# Sheet1.net
KiCad netlist of a schematic drawn in Altium Designer
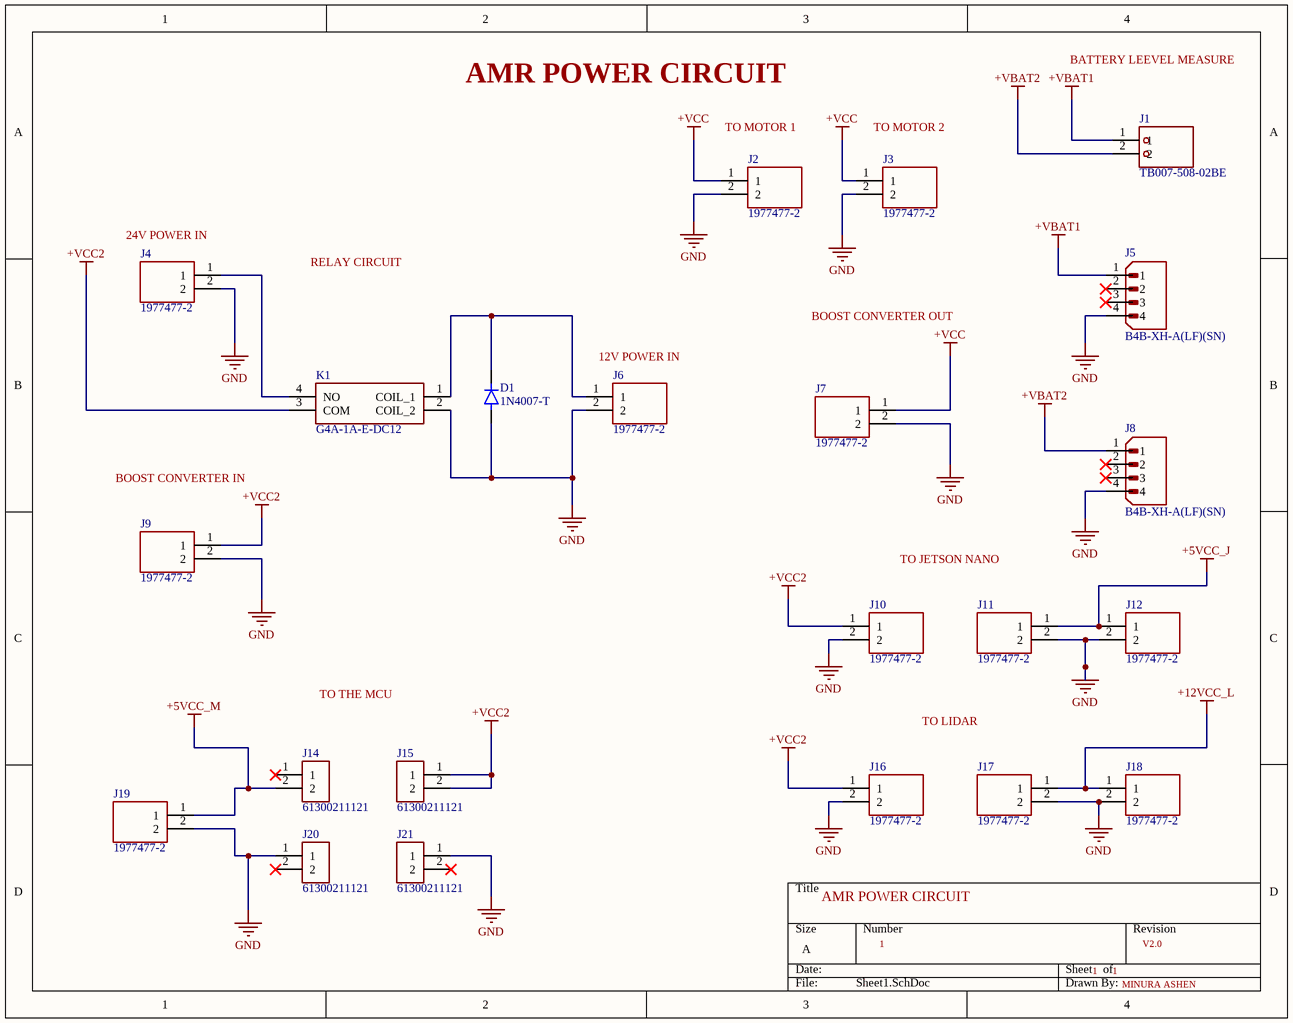
[diagram p0: Sheet1.SchDoc]

(export (version "E")
  (design (tool "Eeschema 10.0.6"))
  (components
    (comp (ref "D1")
      (value "1N4007-T")
      (footprint "DIOAD780W78L463D236")
      (description "Diode Standard 1000 V 1A Through Hole DO-41")
      (fields (field (name "MF") "Yangjie Technology") (field (name "MP") "1N4007"))
      (libsource (lib "Schlib2") (part "1N4007-T"))
    )
    (comp (ref "J1")
      (value "TB007-508-02BE")
      (footprint "CUI_TB007-508-02BE")
      (description "2~24 Poles, Screw Type, Horizontal, 5.08 Pitch, 24~12 (AWG), Terminal Block Connector")
      (fields (field (name "MF") "Same Sky"))
      (libsource (lib "Schlib2") (part "TB007-508-02BE"))
    )
    (comp (ref "J2")
      (value "1977477-2")
      (footprint "TE_1977477-2")
      (description "Buchanan, Module Dual Barrier, .325 CL, 2 Pos. ¦ TE Connectivity 1977477-2")
      (fields (field (name "MF") "TE Connectivity"))
      (libsource (lib "Schlib2") (part "1977477-2"))
    )
    (comp (ref "J3")
      (value "1977477-2")
      (footprint "TE_1977477-2")
      (description "Buchanan, Module Dual Barrier, .325 CL, 2 Pos. ¦ TE Connectivity 1977477-2")
      (fields (field (name "MF") "TE Connectivity"))
      (libsource (lib "Schlib2") (part "1977477-2"))
    )
    (comp (ref "J4")
      (value "1977477-2")
      (footprint "TE_1977477-2")
      (description "Buchanan, Module Dual Barrier, .325 CL, 2 Pos. ¦ TE Connectivity 1977477-2")
      (fields (field (name "MF") "TE Connectivity"))
      (libsource (lib "") (part "1977477-2_1"))
    )
    (comp (ref "J5")
      (value "B4B-XH-A(LF)(SN)")
      (footprint "JST_B4B-XH-A(LF)(SN)")
      (description "Connector Header Through Hole 4 position 0.098 (2.50mm)")
      (fields (field (name "MF") "JST Sales"))
      (libsource (lib "Schlib2") (part "B4B-XH-A(LF)(SN)"))
    )
    (comp (ref "J6")
      (value "1977477-2")
      (footprint "TE_1977477-2")
      (description "Buchanan, Module Dual Barrier, .325 CL, 2 Pos. ¦ TE Connectivity 1977477-2")
      (fields (field (name "MF") "TE Connectivity"))
      (libsource (lib "Schlib2") (part "1977477-2"))
    )
    (comp (ref "J7")
      (value "1977477-2")
      (footprint "TE_1977477-2")
      (description "Buchanan, Module Dual Barrier, .325 CL, 2 Pos. ¦ TE Connectivity 1977477-2")
      (fields (field (name "MF") "TE Connectivity"))
      (libsource (lib "") (part "1977477-2_1"))
    )
    (comp (ref "J8")
      (value "B4B-XH-A(LF)(SN)")
      (footprint "JST_B4B-XH-A(LF)(SN)")
      (description "Connector Header Through Hole 4 position 0.098 (2.50mm)")
      (fields (field (name "MF") "JST Sales"))
      (libsource (lib "Schlib2") (part "B4B-XH-A(LF)(SN)"))
    )
    (comp (ref "J9")
      (value "1977477-2")
      (footprint "TE_1977477-2")
      (description "Buchanan, Module Dual Barrier, .325 CL, 2 Pos. ¦ TE Connectivity 1977477-2")
      (fields (field (name "MF") "TE Connectivity"))
      (libsource (lib "") (part "1977477-2_1"))
    )
    (comp (ref "J10")
      (value "1977477-2")
      (footprint "TE_1977477-2")
      (description "Buchanan, Module Dual Barrier, .325 CL, 2 Pos. ¦ TE Connectivity 1977477-2")
      (fields (field (name "MF") "TE Connectivity"))
      (libsource (lib "Schlib2") (part "1977477-2"))
    )
    (comp (ref "J11")
      (value "1977477-2")
      (footprint "TE_1977477-2")
      (description "Buchanan, Module Dual Barrier, .325 CL, 2 Pos. ¦ TE Connectivity 1977477-2")
      (fields (field (name "MF") "TE Connectivity"))
      (libsource (lib "") (part "1977477-2_1"))
    )
    (comp (ref "J12")
      (value "1977477-2")
      (footprint "TE_1977477-2")
      (description "Buchanan, Module Dual Barrier, .325 CL, 2 Pos. ¦ TE Connectivity 1977477-2")
      (fields (field (name "MF") "TE Connectivity"))
      (libsource (lib "Schlib2") (part "1977477-2"))
    )
    (comp (ref "J14")
      (value "61300211121")
      (footprint "HDRV2W110P0X254_1X2_508X254X854P")
      (description "WURTH ELEKTRONIK - 61300211121 - HEADER, 2.54MM, PIN, THT, VERTICAL, 2WAY")
      (fields (field (name "MOUSER PART NUMBER") "710-61300211121"))
      (libsource (lib "Schlib2") (part "61300211121"))
    )
    (comp (ref "J15")
      (value "61300211121")
      (footprint "HDRV2W110P0X254_1X2_508X254X854P")
      (description "WURTH ELEKTRONIK - 61300211121 - HEADER, 2.54MM, PIN, THT, VERTICAL, 2WAY")
      (fields (field (name "MOUSER PART NUMBER") "710-61300211121"))
      (libsource (lib "") (part "61300211121_1"))
    )
    (comp (ref "J16")
      (value "1977477-2")
      (footprint "TE_1977477-2")
      (description "Buchanan, Module Dual Barrier, .325 CL, 2 Pos. ¦ TE Connectivity 1977477-2")
      (fields (field (name "MF") "TE Connectivity"))
      (libsource (lib "Schlib2") (part "1977477-2"))
    )
    (comp (ref "J17")
      (value "1977477-2")
      (footprint "TE_1977477-2")
      (description "Buchanan, Module Dual Barrier, .325 CL, 2 Pos. ¦ TE Connectivity 1977477-2")
      (fields (field (name "MF") "TE Connectivity"))
      (libsource (lib "") (part "1977477-2_1"))
    )
    (comp (ref "J18")
      (value "1977477-2")
      (footprint "TE_1977477-2")
      (description "Buchanan, Module Dual Barrier, .325 CL, 2 Pos. ¦ TE Connectivity 1977477-2")
      (fields (field (name "MF") "TE Connectivity"))
      (libsource (lib "Schlib2") (part "1977477-2"))
    )
    (comp (ref "J19")
      (value "1977477-2")
      (footprint "TE_1977477-2")
      (description "Buchanan, Module Dual Barrier, .325 CL, 2 Pos. ¦ TE Connectivity 1977477-2")
      (fields (field (name "MF") "TE Connectivity"))
      (libsource (lib "") (part "1977477-2_1"))
    )
    (comp (ref "J20")
      (value "61300211121")
      (footprint "HDRV2W110P0X254_1X2_508X254X854P")
      (description "WURTH ELEKTRONIK - 61300211121 - HEADER, 2.54MM, PIN, THT, VERTICAL, 2WAY")
      (fields (field (name "MOUSER PART NUMBER") "710-61300211121"))
      (libsource (lib "Schlib2") (part "61300211121"))
    )
    (comp (ref "J21")
      (value "61300211121")
      (footprint "HDRV2W110P0X254_1X2_508X254X854P")
      (description "WURTH ELEKTRONIK - 61300211121 - HEADER, 2.54MM, PIN, THT, VERTICAL, 2WAY")
      (fields (field (name "MOUSER PART NUMBER") "710-61300211121"))
      (libsource (lib "") (part "61300211121_1"))
    )
    (comp (ref "K1")
      (value "G4A-1A-E-DC12")
      (footprint "G4A1AEDC12")
      (description "General Purpose Relays SPST-NO 12VDC PCB & QC")
      (fields (field (name "MOUSER PART NUMBER") "653-G4A-1AE-DC12"))
      (libsource (lib "Schlib2") (part "G4A-1A-E-DC12"))
    )
  )
  (nets
    (net (code "1") (name "+5VCC_J") (class "Default")
      (node (ref "J11") (pin "1") (pinfunction "1_1") (pintype "passive"))
      (node (ref "J12") (pin "1") (pinfunction "1_1") (pintype "passive"))
    )
    (net (code "2") (name "+5VCC_M") (class "Default")
      (node (ref "J14") (pin "2") (pinfunction "2_2") (pintype "passive"))
      (node (ref "J19") (pin "1") (pinfunction "1_1") (pintype "passive"))
    )
    (net (code "3") (name "+12VCC_L") (class "Default")
      (node (ref "J17") (pin "1") (pinfunction "1_1") (pintype "passive"))
      (node (ref "J18") (pin "1") (pinfunction "1_1") (pintype "passive"))
    )
    (net (code "4") (name "+VBAT1") (class "Default")
      (node (ref "J1") (pin "1") (pinfunction "1_1") (pintype "passive"))
      (node (ref "J5") (pin "1") (pinfunction "1_1") (pintype "passive"))
    )
    (net (code "5") (name "+VBAT2") (class "Default")
      (node (ref "J1") (pin "2") (pinfunction "2_2") (pintype "passive"))
      (node (ref "J8") (pin "1") (pinfunction "1_1") (pintype "passive"))
    )
    (net (code "6") (name "+VCC") (class "Default")
      (node (ref "J2") (pin "1") (pinfunction "1_1") (pintype "passive"))
      (node (ref "J3") (pin "1") (pinfunction "1_1") (pintype "passive"))
      (node (ref "J7") (pin "1") (pinfunction "1_1") (pintype "passive"))
    )
    (net (code "7") (name "+VCC2") (class "Default")
      (node (ref "J10") (pin "1") (pinfunction "1_1") (pintype "passive"))
      (node (ref "J15") (pin "1") (pinfunction "1_1") (pintype "passive"))
      (node (ref "J15") (pin "2") (pinfunction "2_2") (pintype "passive"))
      (node (ref "J16") (pin "1") (pinfunction "1_1") (pintype "passive"))
      (node (ref "J9") (pin "1") (pinfunction "1_1") (pintype "passive"))
      (node (ref "K1") (pin "3") (pinfunction "COM_3") (pintype "passive"))
    )
    (net (code "8") (name "GND") (class "Default")
      (node (ref "D1") (pin "A") (pinfunction "A_A") (pintype "passive"))
      (node (ref "J10") (pin "2") (pinfunction "2_2") (pintype "passive"))
      (node (ref "J11") (pin "2") (pinfunction "2_2") (pintype "passive"))
      (node (ref "J12") (pin "2") (pinfunction "2_2") (pintype "passive"))
      (node (ref "J16") (pin "2") (pinfunction "2_2") (pintype "passive"))
      (node (ref "J17") (pin "2") (pinfunction "2_2") (pintype "passive"))
      (node (ref "J18") (pin "2") (pinfunction "2_2") (pintype "passive"))
      (node (ref "J19") (pin "2") (pinfunction "2_2") (pintype "passive"))
      (node (ref "J2") (pin "2") (pinfunction "2_2") (pintype "passive"))
      (node (ref "J20") (pin "1") (pinfunction "1_1") (pintype "passive"))
      (node (ref "J21") (pin "1") (pinfunction "1_1") (pintype "passive"))
      (node (ref "J3") (pin "2") (pinfunction "2_2") (pintype "passive"))
      (node (ref "J4") (pin "2") (pinfunction "2_2") (pintype "passive"))
      (node (ref "J5") (pin "4") (pinfunction "4_4") (pintype "passive"))
      (node (ref "J6") (pin "2") (pinfunction "2_2") (pintype "passive"))
      (node (ref "J7") (pin "2") (pinfunction "2_2") (pintype "passive"))
      (node (ref "J8") (pin "4") (pinfunction "4_4") (pintype "passive"))
      (node (ref "J9") (pin "2") (pinfunction "2_2") (pintype "passive"))
      (node (ref "K1") (pin "2") (pinfunction "COIL_2_2") (pintype "passive"))
    )
    (net (code "9") (name "Net-(K1-COIL_1)") (class "Default")
      (node (ref "D1") (pin "K") (pinfunction "K_K") (pintype "passive"))
      (node (ref "J6") (pin "1") (pinfunction "1_1") (pintype "passive"))
      (node (ref "K1") (pin "1") (pinfunction "COIL_1_1") (pintype "passive"))
    )
    (net (code "10") (name "Net-(K1-NO)") (class "Default")
      (node (ref "J4") (pin "1") (pinfunction "1_1") (pintype "passive"))
      (node (ref "K1") (pin "4") (pinfunction "NO_4") (pintype "passive"))
    )
    (net (code "11") (name "unconnected-(J5-Pad2)") (class "Default")
      (node (ref "J5") (pin "2") (pinfunction "2_2") (pintype "passive+no_connect"))
    )
    (net (code "12") (name "unconnected-(J5-Pad3)") (class "Default")
      (node (ref "J5") (pin "3") (pinfunction "3_3") (pintype "passive+no_connect"))
    )
    (net (code "13") (name "unconnected-(J8-Pad2)") (class "Default")
      (node (ref "J8") (pin "2") (pinfunction "2_2") (pintype "passive+no_connect"))
    )
    (net (code "14") (name "unconnected-(J8-Pad3)") (class "Default")
      (node (ref "J8") (pin "3") (pinfunction "3_3") (pintype "passive+no_connect"))
    )
    (net (code "15") (name "unconnected-(J14-Pad1)") (class "Default")
      (node (ref "J14") (pin "1") (pinfunction "1_1") (pintype "passive+no_connect"))
    )
    (net (code "16") (name "unconnected-(J20-Pad2)") (class "Default")
      (node (ref "J20") (pin "2") (pinfunction "2_2") (pintype "passive+no_connect"))
    )
    (net (code "17") (name "unconnected-(J21-Pad2)") (class "Default")
      (node (ref "J21") (pin "2") (pinfunction "2_2") (pintype "passive+no_connect"))
    )
  )
)
